# Superbot_hbridge_mk3.net
KiCad netlist of a schematic drawn in Altium Designer
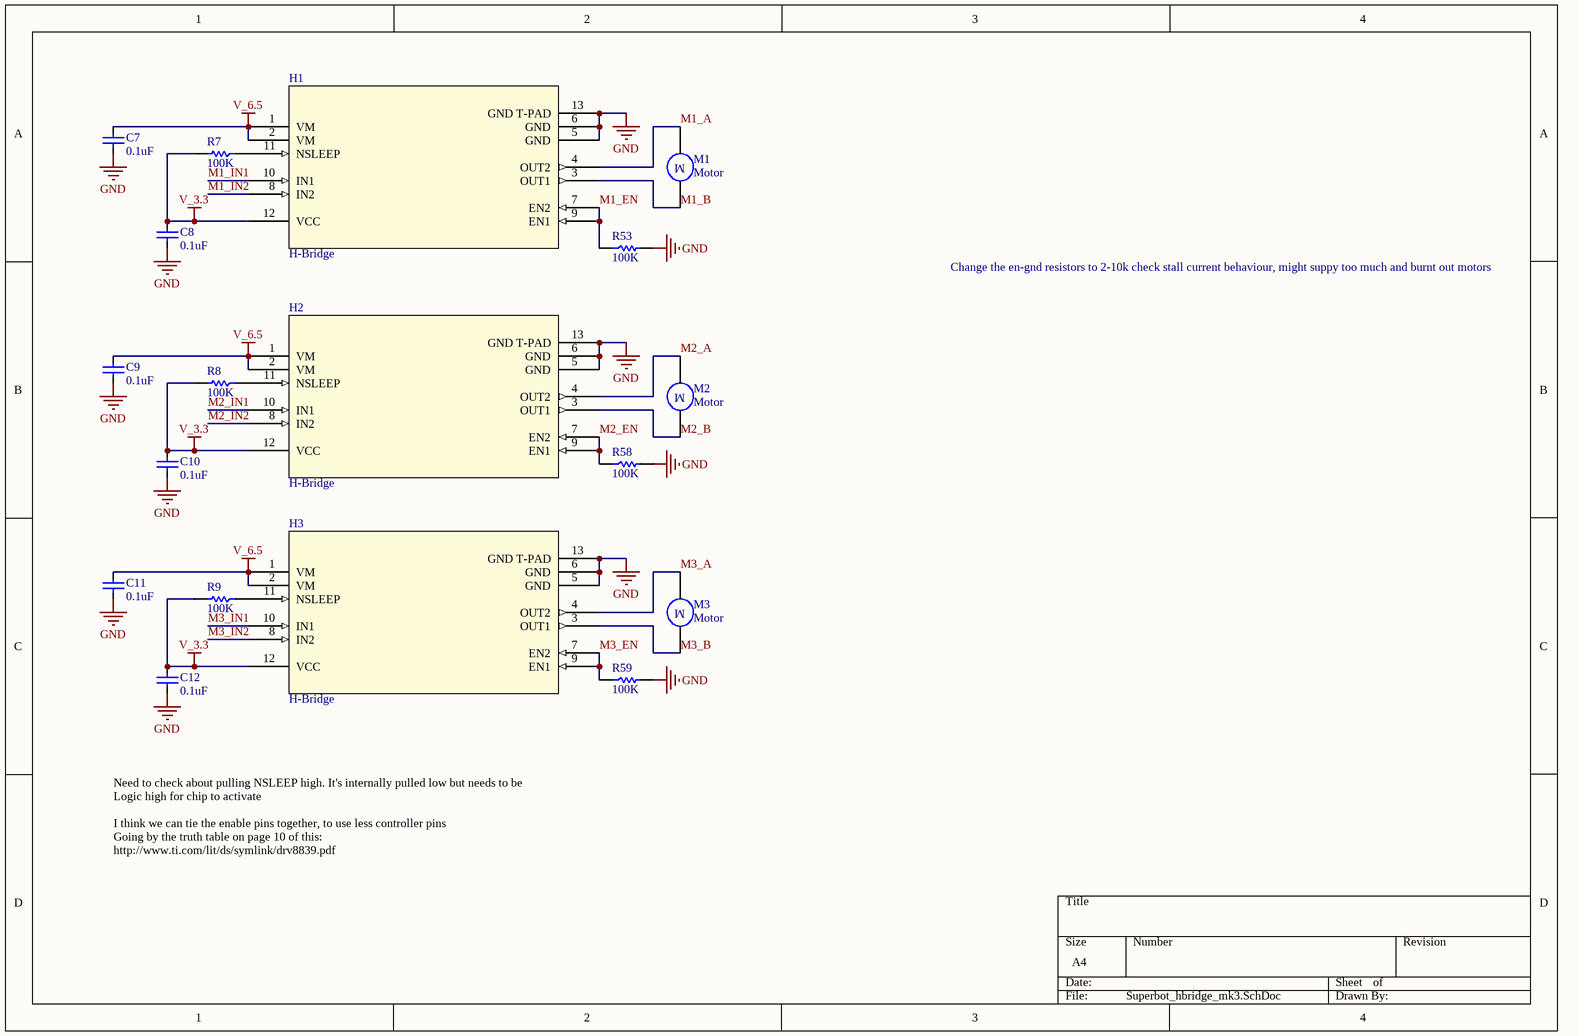
[diagram p0: Superbot_hbridge_mk3.SchDoc]

(export (version "E")
  (design (tool "Eeschema 10.0.6"))
  (components
    (comp (ref "C7")
      (value "0.1uF")
      (footprint "CAP0603R")
      (description "Capacitor")
      (fields
        (field (name "MANUFACTURER") "Microchip Technology")
        (field (name "MANUFACTURER PART NUM") "MIC5378YC5-TR")
      )
      (libsource (lib "SuperBot_Schlib1") (part "C"))
    )
    (comp (ref "C8")
      (value "0.1uF")
      (footprint "CAP0603R")
      (description "Capacitor")
      (fields
        (field (name "MANUFACTURER") "Microchip Technology")
        (field (name "MANUFACTURER PART NUM") "MIC5378YC5-TR")
      )
      (libsource (lib "SuperBot_Schlib1") (part "C"))
    )
    (comp (ref "C9")
      (value "0.1uF")
      (footprint "CAP0603R")
      (description "Capacitor")
      (fields
        (field (name "MANUFACTURER") "Microchip Technology")
        (field (name "MANUFACTURER PART NUM") "MIC5378YC5-TR")
      )
      (libsource (lib "SuperBot_Schlib1") (part "C"))
    )
    (comp (ref "C10")
      (value "0.1uF")
      (footprint "CAP0603R")
      (description "Capacitor")
      (fields
        (field (name "MANUFACTURER") "Microchip Technology")
        (field (name "MANUFACTURER PART NUM") "MIC5378YC5-TR")
      )
      (libsource (lib "SuperBot_Schlib1") (part "C"))
    )
    (comp (ref "C11")
      (value "0.1uF")
      (footprint "CAP0603R")
      (description "Capacitor")
      (fields
        (field (name "MANUFACTURER") "Microchip Technology")
        (field (name "MANUFACTURER PART NUM") "MIC5378YC5-TR")
      )
      (libsource (lib "SuperBot_Schlib1") (part "C"))
    )
    (comp (ref "C12")
      (value "0.1uF")
      (footprint "CAP0603R")
      (description "Capacitor")
      (fields
        (field (name "MANUFACTURER") "Microchip Technology")
        (field (name "MANUFACTURER PART NUM") "MIC5378YC5-TR")
      )
      (libsource (lib "SuperBot_Schlib1") (part "C"))
    )
    (comp (ref "H1")
      (value "H-Bridge")
      (footprint "WSON_0.8mm_DSS0012A")
      (description "1.8A , Half Bridge (2), Driver - Fully Integrated, Control and Power Stage")
      (fields
        (field (name "MANUFACTURER") "Texas Instruments")
        (field (name "MANUFACTURER PART NUM") "DRV8839DSSR")
      )
      (libsource (lib "SuperBot_Schlib1") (part "DRV8839DSSR"))
    )
    (comp (ref "H2")
      (value "H-Bridge")
      (footprint "WSON_0.8mm_DSS0012A")
      (description "1.8A , Half Bridge (2), Driver - Fully Integrated, Control and Power Stage")
      (fields
        (field (name "MANUFACTURER") "Texas Instruments")
        (field (name "MANUFACTURER PART NUM") "DRV8839DSSR")
      )
      (libsource (lib "SuperBot_Schlib1") (part "DRV8839DSSR"))
    )
    (comp (ref "H3")
      (value "H-Bridge")
      (footprint "WSON_0.8mm_DSS0012A")
      (description "1.8A , Half Bridge (2), Driver - Fully Integrated, Control and Power Stage")
      (fields
        (field (name "MANUFACTURER") "Texas Instruments")
        (field (name "MANUFACTURER PART NUM") "DRV8839DSSR")
      )
      (libsource (lib "SuperBot_Schlib1") (part "DRV8839DSSR"))
    )
    (comp (ref "M1")
      (value "Motor")
      (footprint "MicroMotor_TypeA")
      (libsource (lib "SuperBot_Schlib1") (part "Motor"))
    )
    (comp (ref "M2")
      (value "Motor")
      (footprint "MicroMotor_TypeA")
      (libsource (lib "SuperBot_Schlib1") (part "Motor"))
    )
    (comp (ref "M3")
      (value "Motor")
      (footprint "MicroMotor_TypeA")
      (libsource (lib "SuperBot_Schlib1") (part "Motor"))
    )
    (comp (ref "R7")
      (value "100K")
      (footprint "RES0603R")
      (description "Resistor")
      (libsource (lib "SuperBot_Schlib1") (part "R"))
    )
    (comp (ref "R8")
      (value "100K")
      (footprint "RES0603R")
      (description "Resistor")
      (libsource (lib "SuperBot_Schlib1") (part "R"))
    )
    (comp (ref "R9")
      (value "100K")
      (footprint "RES0603R")
      (description "Resistor")
      (libsource (lib "SuperBot_Schlib1") (part "R"))
    )
    (comp (ref "R53")
      (value "100K")
      (footprint "RES0603R")
      (description "Resistor")
      (libsource (lib "SuperBot_Schlib1") (part "R"))
    )
    (comp (ref "R58")
      (value "100K")
      (footprint "RES0603R")
      (description "Resistor")
      (libsource (lib "SuperBot_Schlib1") (part "R"))
    )
    (comp (ref "R59")
      (value "100K")
      (footprint "RES0603R")
      (description "Resistor")
      (libsource (lib "SuperBot_Schlib1") (part "R"))
    )
  )
  (nets
    (net (code "1") (name "/M1_A") (class "Default")
      (node (ref "H1") (pin "4") (pinfunction "OUT2_4") (pintype "output"))
      (node (ref "M1") (pin "2") (pintype "passive"))
    )
    (net (code "2") (name "/M1_B") (class "Default")
      (node (ref "H1") (pin "3") (pinfunction "OUT1_3") (pintype "output"))
      (node (ref "M1") (pin "1") (pintype "passive"))
    )
    (net (code "3") (name "/M1_EN") (class "Default")
      (node (ref "H1") (pin "7") (pinfunction "EN2_7") (pintype "input"))
      (node (ref "H1") (pin "9") (pinfunction "EN1_9") (pintype "input"))
      (node (ref "R53") (pin "1") (pintype "passive"))
    )
    (net (code "4") (name "/M1_IN1") (class "Default")
      (node (ref "H1") (pin "10") (pinfunction "IN1_10") (pintype "input"))
    )
    (net (code "5") (name "/M1_IN2") (class "Default")
      (node (ref "H1") (pin "8") (pinfunction "IN2_8") (pintype "input"))
    )
    (net (code "6") (name "/M2_A") (class "Default")
      (node (ref "H2") (pin "4") (pinfunction "OUT2_4") (pintype "output"))
      (node (ref "M2") (pin "2") (pintype "passive"))
    )
    (net (code "7") (name "/M2_B") (class "Default")
      (node (ref "H2") (pin "3") (pinfunction "OUT1_3") (pintype "output"))
      (node (ref "M2") (pin "1") (pintype "passive"))
    )
    (net (code "8") (name "/M2_EN") (class "Default")
      (node (ref "H2") (pin "7") (pinfunction "EN2_7") (pintype "input"))
      (node (ref "H2") (pin "9") (pinfunction "EN1_9") (pintype "input"))
      (node (ref "R58") (pin "1") (pintype "passive"))
    )
    (net (code "9") (name "/M2_IN1") (class "Default")
      (node (ref "H2") (pin "10") (pinfunction "IN1_10") (pintype "input"))
    )
    (net (code "10") (name "/M2_IN2") (class "Default")
      (node (ref "H2") (pin "8") (pinfunction "IN2_8") (pintype "input"))
    )
    (net (code "11") (name "/M3_A") (class "Default")
      (node (ref "H3") (pin "4") (pinfunction "OUT2_4") (pintype "output"))
      (node (ref "M3") (pin "2") (pintype "passive"))
    )
    (net (code "12") (name "/M3_B") (class "Default")
      (node (ref "H3") (pin "3") (pinfunction "OUT1_3") (pintype "output"))
      (node (ref "M3") (pin "1") (pintype "passive"))
    )
    (net (code "13") (name "/M3_EN") (class "Default")
      (node (ref "H3") (pin "7") (pinfunction "EN2_7") (pintype "input"))
      (node (ref "H3") (pin "9") (pinfunction "EN1_9") (pintype "input"))
      (node (ref "R59") (pin "1") (pintype "passive"))
    )
    (net (code "14") (name "/M3_IN1") (class "Default")
      (node (ref "H3") (pin "10") (pinfunction "IN1_10") (pintype "input"))
    )
    (net (code "15") (name "/M3_IN2") (class "Default")
      (node (ref "H3") (pin "8") (pinfunction "IN2_8") (pintype "input"))
    )
    (net (code "16") (name "GND") (class "Default")
      (node (ref "C10") (pin "2") (pinfunction "2_2") (pintype "passive"))
      (node (ref "C11") (pin "2") (pinfunction "2_2") (pintype "passive"))
      (node (ref "C12") (pin "2") (pinfunction "2_2") (pintype "passive"))
      (node (ref "C7") (pin "2") (pinfunction "2_2") (pintype "passive"))
      (node (ref "C8") (pin "2") (pinfunction "2_2") (pintype "passive"))
      (node (ref "C9") (pin "2") (pinfunction "2_2") (pintype "passive"))
      (node (ref "H1") (pin "13") (pinfunction "GND_T-PAD_13") (pintype "passive"))
      (node (ref "H1") (pin "5") (pinfunction "GND_5") (pintype "power_in"))
      (node (ref "H1") (pin "6") (pinfunction "GND_6") (pintype "power_in"))
      (node (ref "H2") (pin "13") (pinfunction "GND_T-PAD_13") (pintype "passive"))
      (node (ref "H2") (pin "5") (pinfunction "GND_5") (pintype "power_in"))
      (node (ref "H2") (pin "6") (pinfunction "GND_6") (pintype "power_in"))
      (node (ref "H3") (pin "13") (pinfunction "GND_T-PAD_13") (pintype "passive"))
      (node (ref "H3") (pin "5") (pinfunction "GND_5") (pintype "power_in"))
      (node (ref "H3") (pin "6") (pinfunction "GND_6") (pintype "power_in"))
      (node (ref "R53") (pin "2") (pintype "passive"))
      (node (ref "R58") (pin "2") (pintype "passive"))
      (node (ref "R59") (pin "2") (pintype "passive"))
    )
    (net (code "17") (name "Net-(H1-NSLEEP)") (class "Default")
      (node (ref "H1") (pin "11") (pinfunction "NSLEEP_11") (pintype "input"))
      (node (ref "R7") (pin "1") (pintype "passive"))
    )
    (net (code "18") (name "Net-(H2-NSLEEP)") (class "Default")
      (node (ref "H2") (pin "11") (pinfunction "NSLEEP_11") (pintype "input"))
      (node (ref "R8") (pin "1") (pintype "passive"))
    )
    (net (code "19") (name "Net-(H3-NSLEEP)") (class "Default")
      (node (ref "H3") (pin "11") (pinfunction "NSLEEP_11") (pintype "input"))
      (node (ref "R9") (pin "1") (pintype "passive"))
    )
    (net (code "20") (name "V_3.3") (class "Default")
      (node (ref "C10") (pin "1") (pinfunction "1_1") (pintype "passive"))
      (node (ref "C12") (pin "1") (pinfunction "1_1") (pintype "passive"))
      (node (ref "C8") (pin "1") (pinfunction "1_1") (pintype "passive"))
      (node (ref "H1") (pin "12") (pinfunction "VCC_12") (pintype "power_in"))
      (node (ref "H2") (pin "12") (pinfunction "VCC_12") (pintype "power_in"))
      (node (ref "H3") (pin "12") (pinfunction "VCC_12") (pintype "power_in"))
      (node (ref "R7") (pin "2") (pintype "passive"))
      (node (ref "R8") (pin "2") (pintype "passive"))
      (node (ref "R9") (pin "2") (pintype "passive"))
    )
    (net (code "21") (name "V_6.5") (class "Default")
      (node (ref "C11") (pin "1") (pinfunction "1_1") (pintype "passive"))
      (node (ref "C7") (pin "1") (pinfunction "1_1") (pintype "passive"))
      (node (ref "C9") (pin "1") (pinfunction "1_1") (pintype "passive"))
      (node (ref "H1") (pin "1") (pinfunction "VM_1") (pintype "power_in"))
      (node (ref "H1") (pin "2") (pinfunction "VM_2") (pintype "power_in"))
      (node (ref "H2") (pin "1") (pinfunction "VM_1") (pintype "power_in"))
      (node (ref "H2") (pin "2") (pinfunction "VM_2") (pintype "power_in"))
      (node (ref "H3") (pin "1") (pinfunction "VM_1") (pintype "power_in"))
      (node (ref "H3") (pin "2") (pinfunction "VM_2") (pintype "power_in"))
    )
  )
)
